# SparkFun_MP3_Breakout-VS1033D.net
KiCad netlist of a schematic drawn in EAGLE
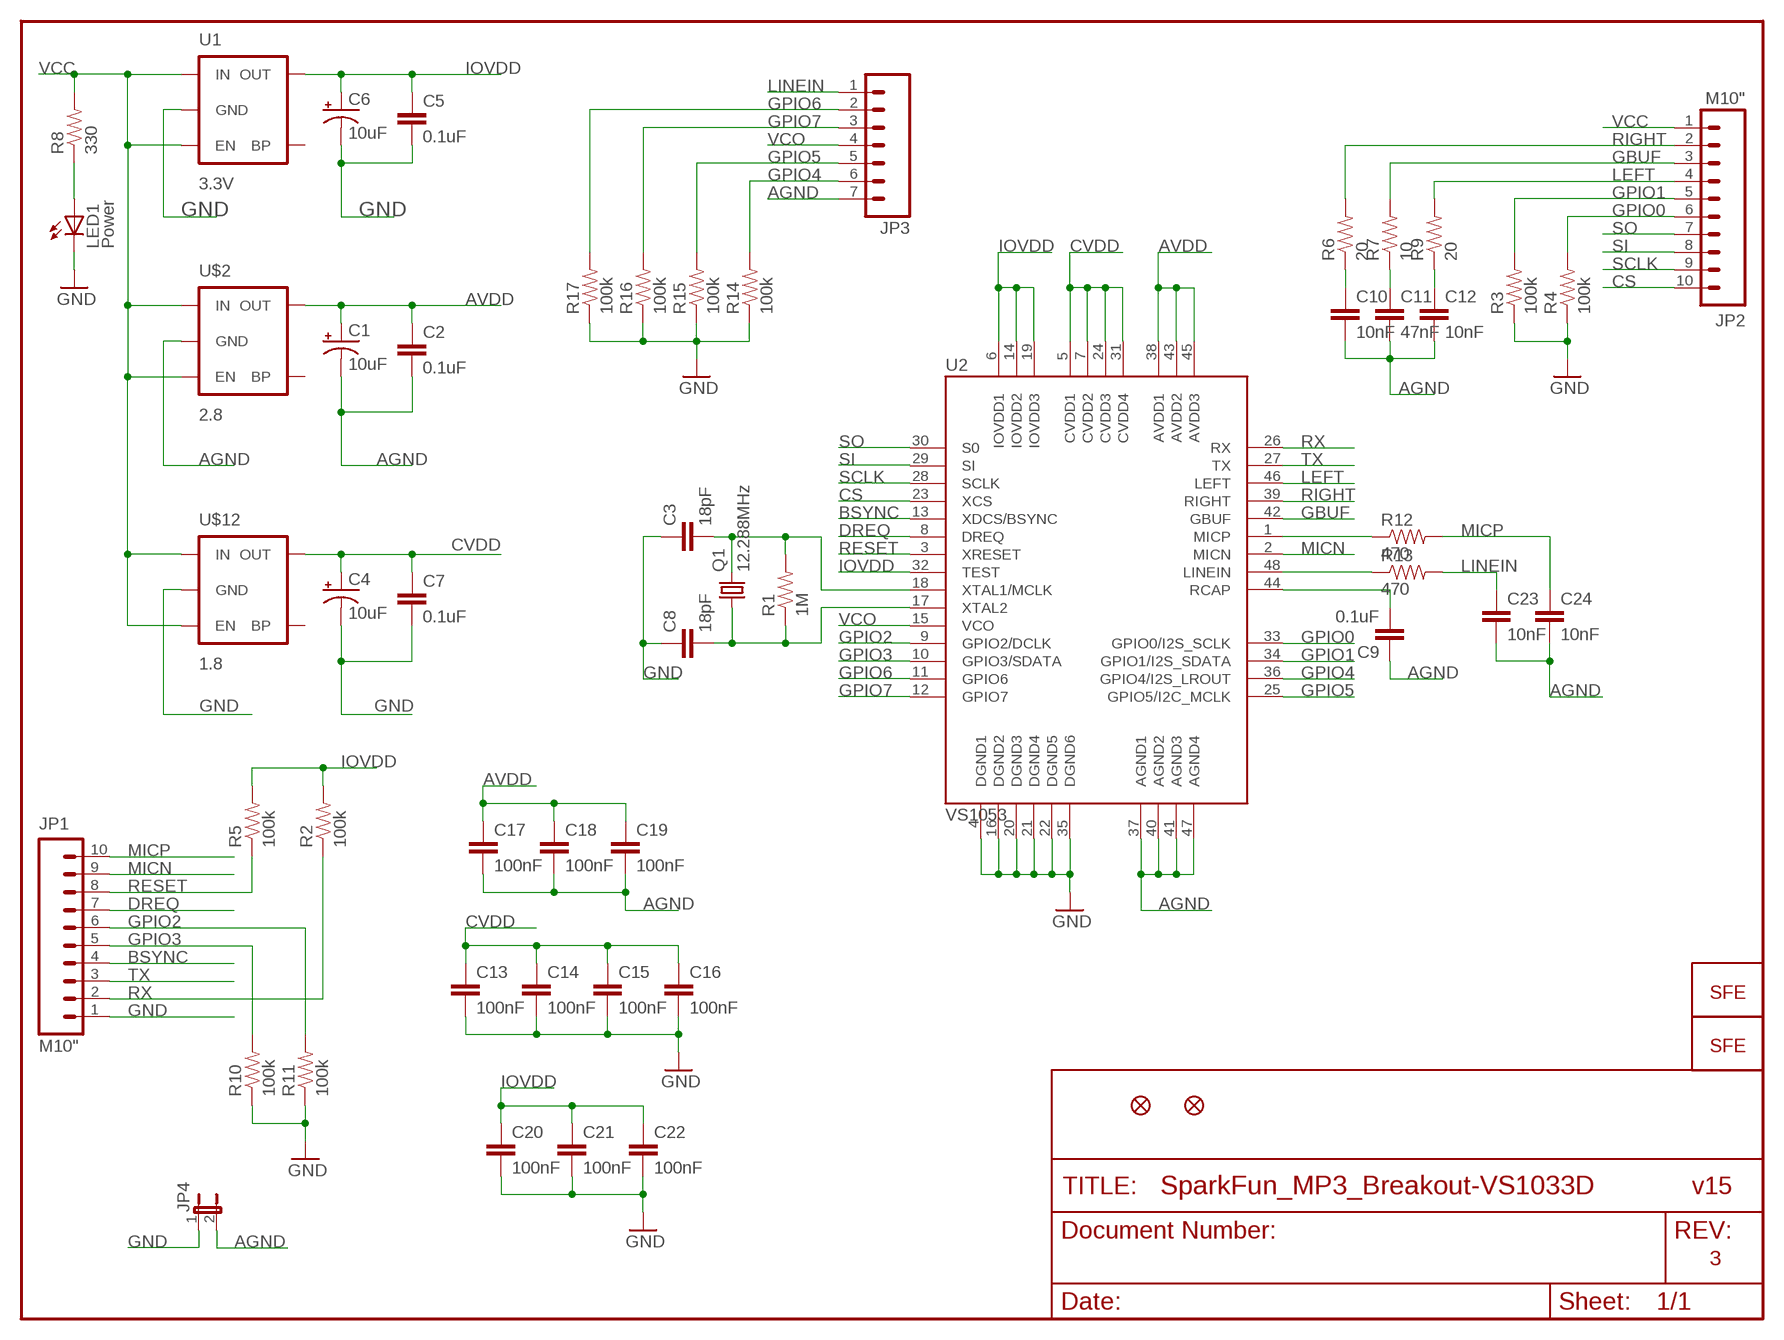
[diagram p0: schematic, sheet 1]

(export (version "E")
  (design (tool "Eeschema 10.0.6"))
  (components
    (comp (ref "C1")
      (value "10uF")
      (footprint "eagle-import:EIA3216")
      (libsource (lib "eagle-import") (part "CAP_POL1206"))
    )
    (comp (ref "C2")
      (value "0.1uF")
      (footprint "eagle-import:0402-CAP")
      (libsource (lib "eagle-import") (part "CAP0402-CAP"))
    )
    (comp (ref "C3")
      (value "18pF")
      (footprint "eagle-import:0402-CAP")
      (libsource (lib "eagle-import") (part "CAP0402-CAP"))
    )
    (comp (ref "C4")
      (value "10uF")
      (footprint "eagle-import:EIA3216")
      (libsource (lib "eagle-import") (part "CAP_POL1206"))
    )
    (comp (ref "C5")
      (value "0.1uF")
      (footprint "eagle-import:0402-CAP")
      (libsource (lib "eagle-import") (part "CAP0402-CAP"))
    )
    (comp (ref "C6")
      (value "10uF")
      (footprint "eagle-import:EIA3216")
      (libsource (lib "eagle-import") (part "CAP_POL1206"))
    )
    (comp (ref "C7")
      (value "0.1uF")
      (footprint "eagle-import:0402-CAP")
      (libsource (lib "eagle-import") (part "CAP0402-CAP"))
    )
    (comp (ref "C8")
      (value "18pF")
      (footprint "eagle-import:0402-CAP")
      (libsource (lib "eagle-import") (part "CAP0402-CAP"))
    )
    (comp (ref "C9")
      (value "0.1uF")
      (footprint "eagle-import:0402-CAP")
      (libsource (lib "eagle-import") (part "CAP0402-CAP"))
    )
    (comp (ref "C10")
      (value "10nF")
      (footprint "eagle-import:0402-CAP")
      (libsource (lib "eagle-import") (part "CAP0402-CAP"))
    )
    (comp (ref "C11")
      (value "47nF")
      (footprint "eagle-import:0402-CAP")
      (libsource (lib "eagle-import") (part "CAP0402-CAP"))
    )
    (comp (ref "C12")
      (value "10nF")
      (footprint "eagle-import:0402-CAP")
      (libsource (lib "eagle-import") (part "CAP0402-CAP"))
    )
    (comp (ref "C13")
      (value "100nF")
      (footprint "eagle-import:0402-CAP")
      (libsource (lib "eagle-import") (part "CAP0402-CAP"))
    )
    (comp (ref "C14")
      (value "100nF")
      (footprint "eagle-import:0402-CAP")
      (libsource (lib "eagle-import") (part "CAP0402-CAP"))
    )
    (comp (ref "C15")
      (value "100nF")
      (footprint "eagle-import:0402-CAP")
      (libsource (lib "eagle-import") (part "CAP0402-CAP"))
    )
    (comp (ref "C16")
      (value "100nF")
      (footprint "eagle-import:0402-CAP")
      (libsource (lib "eagle-import") (part "CAP0402-CAP"))
    )
    (comp (ref "C17")
      (value "100nF")
      (footprint "eagle-import:0402-CAP")
      (libsource (lib "eagle-import") (part "CAP0402-CAP"))
    )
    (comp (ref "C18")
      (value "100nF")
      (footprint "eagle-import:0402-CAP")
      (libsource (lib "eagle-import") (part "CAP0402-CAP"))
    )
    (comp (ref "C19")
      (value "100nF")
      (footprint "eagle-import:0402-CAP")
      (libsource (lib "eagle-import") (part "CAP0402-CAP"))
    )
    (comp (ref "C20")
      (value "100nF")
      (footprint "eagle-import:0402-CAP")
      (libsource (lib "eagle-import") (part "CAP0402-CAP"))
    )
    (comp (ref "C21")
      (value "100nF")
      (footprint "eagle-import:0402-CAP")
      (libsource (lib "eagle-import") (part "CAP0402-CAP"))
    )
    (comp (ref "C22")
      (value "100nF")
      (footprint "eagle-import:0402-CAP")
      (libsource (lib "eagle-import") (part "CAP0402-CAP"))
    )
    (comp (ref "C23")
      (value "10nF")
      (footprint "eagle-import:0402-CAP")
      (libsource (lib "eagle-import") (part "CAP0402-CAP"))
    )
    (comp (ref "C24")
      (value "10nF")
      (footprint "eagle-import:0402-CAP")
      (libsource (lib "eagle-import") (part "CAP0402-CAP"))
    )
    (comp (ref "JP1")
      (value "M10\"")
      (footprint "eagle-import:1X10")
      (libsource (lib "eagle-import") (part "M10{dblquote}"))
    )
    (comp (ref "JP2")
      (value "M10\"")
      (footprint "eagle-import:1X10")
      (libsource (lib "eagle-import") (part "M10{dblquote}"))
    )
    (comp (ref "JP3")
      (value "M07")
      (footprint "eagle-import:1X07")
      (libsource (lib "eagle-import") (part "M07"))
    )
    (comp (ref "JP4")
      (value "JUMPER-2SMD-NC")
      (footprint "eagle-import:SJ_2S")
      (libsource (lib "eagle-import") (part "JUMPER-2SMD-NC"))
    )
    (comp (ref "LED1")
      (value "Power")
      (footprint "eagle-import:LED-0603")
      (libsource (lib "eagle-import") (part "LED0603"))
    )
    (comp (ref "Q1")
      (value "12.288MHz")
      (footprint "eagle-import:CRYSTAL-SMD-5X3")
      (libsource (lib "eagle-import") (part "CRYSTAL5X3"))
    )
    (comp (ref "R1")
      (value "1M")
      (footprint "eagle-import:0402-RES")
      (libsource (lib "eagle-import") (part "RESISTOR0402-RES"))
    )
    (comp (ref "R2")
      (value "100k")
      (footprint "eagle-import:0402-RES")
      (libsource (lib "eagle-import") (part "RESISTOR0402-RES"))
    )
    (comp (ref "R3")
      (value "100k")
      (footprint "eagle-import:0402-RES")
      (libsource (lib "eagle-import") (part "RESISTOR0402-RES"))
    )
    (comp (ref "R4")
      (value "100k")
      (footprint "eagle-import:0402-RES")
      (libsource (lib "eagle-import") (part "RESISTOR0402-RES"))
    )
    (comp (ref "R5")
      (value "100k")
      (footprint "eagle-import:0402-RES")
      (libsource (lib "eagle-import") (part "RESISTOR0402-RES"))
    )
    (comp (ref "R6")
      (value "20")
      (footprint "eagle-import:0402-RES")
      (libsource (lib "eagle-import") (part "RESISTOR0402-RES"))
    )
    (comp (ref "R7")
      (value "10")
      (footprint "eagle-import:0402-RES")
      (libsource (lib "eagle-import") (part "RESISTOR0402-RES"))
    )
    (comp (ref "R8")
      (value "330")
      (footprint "eagle-import:0402-RES")
      (libsource (lib "eagle-import") (part "RESISTOR0402-RES"))
    )
    (comp (ref "R9")
      (value "20")
      (footprint "eagle-import:0402-RES")
      (libsource (lib "eagle-import") (part "RESISTOR0402-RES"))
    )
    (comp (ref "R10")
      (value "100k")
      (footprint "eagle-import:0402-RES")
      (libsource (lib "eagle-import") (part "RESISTOR0402-RES"))
    )
    (comp (ref "R11")
      (value "100k")
      (footprint "eagle-import:0402-RES")
      (libsource (lib "eagle-import") (part "RESISTOR0402-RES"))
    )
    (comp (ref "R12")
      (value "470")
      (footprint "eagle-import:0402-RES")
      (libsource (lib "eagle-import") (part "RESISTOR0402-RES"))
    )
    (comp (ref "R13")
      (value "470")
      (footprint "eagle-import:0402-RES")
      (libsource (lib "eagle-import") (part "RESISTOR0402-RES"))
    )
    (comp (ref "R14")
      (value "100k")
      (footprint "eagle-import:0402-RES")
      (libsource (lib "eagle-import") (part "RESISTOR0402-RES"))
    )
    (comp (ref "R15")
      (value "100k")
      (footprint "eagle-import:0402-RES")
      (libsource (lib "eagle-import") (part "RESISTOR0402-RES"))
    )
    (comp (ref "R16")
      (value "100k")
      (footprint "eagle-import:0402-RES")
      (libsource (lib "eagle-import") (part "RESISTOR0402-RES"))
    )
    (comp (ref "R17")
      (value "100k")
      (footprint "eagle-import:0402-RES")
      (libsource (lib "eagle-import") (part "RESISTOR0402-RES"))
    )
    (comp (ref "U$2")
      (value "2.8")
      (footprint "eagle-import:SC70")
      (libsource (lib "eagle-import") (part "V_REG_LDOSMD2"))
    )
    (comp (ref "U$4")
      (value "FIDUCIAL1X2")
      (footprint "eagle-import:FIDUCIAL-1X2")
      (libsource (lib "eagle-import") (part "FIDUCIAL1X2"))
    )
    (comp (ref "U$5")
      (value "FIDUCIAL1X2")
      (footprint "eagle-import:FIDUCIAL-1X2")
      (libsource (lib "eagle-import") (part "FIDUCIAL1X2"))
    )
    (comp (ref "U$6")
      (value "LOGO-SFESK")
      (footprint "eagle-import:SFE-LOGO-FLAME")
      (libsource (lib "eagle-import") (part "LOGO-SFESK"))
    )
    (comp (ref "U$7")
      (value "LOGO-SFENEW")
      (footprint "eagle-import:SFE-NEW-WEBLOGO")
      (libsource (lib "eagle-import") (part "LOGO-SFENEW"))
    )
    (comp (ref "U$12")
      (value "1.8")
      (footprint "eagle-import:SC70")
      (libsource (lib "eagle-import") (part "V_REG_LDOSMD2"))
    )
    (comp (ref "U1")
      (value "3.3V")
      (footprint "eagle-import:SOT23-5")
      (libsource (lib "eagle-import") (part "V_REG_LDOSMD"))
    )
    (comp (ref "U2")
      (value "VS1053")
      (footprint "eagle-import:LQFP-48")
      (libsource (lib "eagle-import") (part "VS1033"))
    )
  )
  (nets
    (net (code "1") (name "/AGND") (class "Default")
      (node (ref "C1") (pin "C") (pinfunction "-_C") (pintype "passive"))
      (node (ref "C10") (pin "2") (pinfunction "2_2") (pintype "passive"))
      (node (ref "C11") (pin "2") (pinfunction "2_2") (pintype "passive"))
      (node (ref "C12") (pin "2") (pinfunction "2_2") (pintype "passive"))
      (node (ref "C17") (pin "2") (pinfunction "2_2") (pintype "passive"))
      (node (ref "C18") (pin "2") (pinfunction "2_2") (pintype "passive"))
      (node (ref "C19") (pin "2") (pinfunction "2_2") (pintype "passive"))
      (node (ref "C2") (pin "2") (pinfunction "2_2") (pintype "passive"))
      (node (ref "C23") (pin "2") (pinfunction "2_2") (pintype "passive"))
      (node (ref "C24") (pin "2") (pinfunction "2_2") (pintype "passive"))
      (node (ref "C9") (pin "1") (pinfunction "1_1") (pintype "passive"))
      (node (ref "JP3") (pin "7") (pinfunction "7_7") (pintype "passive"))
      (node (ref "JP4") (pin "2") (pinfunction "2_2") (pintype "passive"))
      (node (ref "U$2") (pin "2") (pinfunction "GND_2") (pintype "input"))
      (node (ref "U2") (pin "37") (pinfunction "AGND1_37") (pintype "bidirectional"))
      (node (ref "U2") (pin "40") (pinfunction "AGND2_40") (pintype "bidirectional"))
      (node (ref "U2") (pin "41") (pinfunction "AGND3_41") (pintype "bidirectional"))
      (node (ref "U2") (pin "47") (pinfunction "AGND4_47") (pintype "bidirectional"))
    )
    (net (code "2") (name "/AVDD") (class "Default")
      (node (ref "C1") (pin "A") (pinfunction "+_A") (pintype "passive"))
      (node (ref "C17") (pin "1") (pinfunction "1_1") (pintype "passive"))
      (node (ref "C18") (pin "1") (pinfunction "1_1") (pintype "passive"))
      (node (ref "C19") (pin "1") (pinfunction "1_1") (pintype "passive"))
      (node (ref "C2") (pin "1") (pinfunction "1_1") (pintype "passive"))
      (node (ref "U$2") (pin "5") (pinfunction "OUT_5") (pintype "passive"))
      (node (ref "U2") (pin "38") (pinfunction "AVDD1_38") (pintype "bidirectional"))
      (node (ref "U2") (pin "43") (pinfunction "AVDD2_43") (pintype "bidirectional"))
      (node (ref "U2") (pin "45") (pinfunction "AVDD3_45") (pintype "bidirectional"))
    )
    (net (code "3") (name "/BSYNC") (class "Default")
      (node (ref "JP1") (pin "4") (pinfunction "4_4") (pintype "passive"))
      (node (ref "U2") (pin "13") (pinfunction "XDCS/BSYNC_13") (pintype "bidirectional"))
    )
    (net (code "4") (name "/CS") (class "Default")
      (node (ref "JP2") (pin "10") (pinfunction "10_10") (pintype "passive"))
      (node (ref "U2") (pin "23") (pinfunction "XCS_23") (pintype "bidirectional"))
    )
    (net (code "5") (name "/CVDD") (class "Default")
      (node (ref "C13") (pin "1") (pinfunction "1_1") (pintype "passive"))
      (node (ref "C14") (pin "1") (pinfunction "1_1") (pintype "passive"))
      (node (ref "C15") (pin "1") (pinfunction "1_1") (pintype "passive"))
      (node (ref "C16") (pin "1") (pinfunction "1_1") (pintype "passive"))
      (node (ref "C4") (pin "A") (pinfunction "+_A") (pintype "passive"))
      (node (ref "C7") (pin "1") (pinfunction "1_1") (pintype "passive"))
      (node (ref "U$12") (pin "5") (pinfunction "OUT_5") (pintype "passive"))
      (node (ref "U2") (pin "24") (pinfunction "CVDD3_24") (pintype "bidirectional"))
      (node (ref "U2") (pin "31") (pinfunction "CVDD4_31") (pintype "bidirectional"))
      (node (ref "U2") (pin "5") (pinfunction "CVDD1_5") (pintype "bidirectional"))
      (node (ref "U2") (pin "7") (pinfunction "CVDD2_7") (pintype "bidirectional"))
    )
    (net (code "6") (name "/DREQ") (class "Default")
      (node (ref "JP1") (pin "7") (pinfunction "7_7") (pintype "passive"))
      (node (ref "U2") (pin "8") (pinfunction "DREQ_8") (pintype "bidirectional"))
    )
    (net (code "7") (name "/GBUF") (class "Default")
      (node (ref "JP2") (pin "3") (pinfunction "3_3") (pintype "passive"))
      (node (ref "R7") (pin "2") (pinfunction "2_2") (pintype "passive"))
      (node (ref "U2") (pin "42") (pinfunction "GBUF_42") (pintype "bidirectional"))
    )
    (net (code "8") (name "/GPIO0") (class "Default")
      (node (ref "JP2") (pin "6") (pinfunction "6_6") (pintype "passive"))
      (node (ref "R4") (pin "2") (pinfunction "2_2") (pintype "passive"))
      (node (ref "U2") (pin "33") (pinfunction "GPIO0/I2S_SCLK_33") (pintype "bidirectional"))
    )
    (net (code "9") (name "/GPIO1") (class "Default")
      (node (ref "JP2") (pin "5") (pinfunction "5_5") (pintype "passive"))
      (node (ref "R3") (pin "2") (pinfunction "2_2") (pintype "passive"))
      (node (ref "U2") (pin "34") (pinfunction "GPIO1/I2S_SDATA_34") (pintype "bidirectional"))
    )
    (net (code "10") (name "/GPIO2") (class "Default")
      (node (ref "JP1") (pin "6") (pinfunction "6_6") (pintype "passive"))
      (node (ref "R11") (pin "2") (pinfunction "2_2") (pintype "passive"))
      (node (ref "U2") (pin "9") (pinfunction "GPIO2/DCLK_9") (pintype "bidirectional"))
    )
    (net (code "11") (name "/GPIO3") (class "Default")
      (node (ref "JP1") (pin "5") (pinfunction "5_5") (pintype "passive"))
      (node (ref "R10") (pin "2") (pinfunction "2_2") (pintype "passive"))
      (node (ref "U2") (pin "10") (pinfunction "GPIO3/SDATA_10") (pintype "bidirectional"))
    )
    (net (code "12") (name "/GPIO4") (class "Default")
      (node (ref "JP3") (pin "6") (pinfunction "6_6") (pintype "passive"))
      (node (ref "R14") (pin "2") (pinfunction "2_2") (pintype "passive"))
      (node (ref "U2") (pin "36") (pinfunction "GPIO4/I2S_LROUT_36") (pintype "bidirectional"))
    )
    (net (code "13") (name "/GPIO5") (class "Default")
      (node (ref "JP3") (pin "5") (pinfunction "5_5") (pintype "passive"))
      (node (ref "R15") (pin "2") (pinfunction "2_2") (pintype "passive"))
      (node (ref "U2") (pin "25") (pinfunction "GPIO5/I2C_MCLK_25") (pintype "bidirectional"))
    )
    (net (code "14") (name "/GPIO6") (class "Default")
      (node (ref "JP3") (pin "2") (pinfunction "2_2") (pintype "passive"))
      (node (ref "R17") (pin "2") (pinfunction "2_2") (pintype "passive"))
      (node (ref "U2") (pin "11") (pinfunction "GPIO6_11") (pintype "bidirectional"))
    )
    (net (code "15") (name "/GPIO7") (class "Default")
      (node (ref "JP3") (pin "3") (pinfunction "3_3") (pintype "passive"))
      (node (ref "R16") (pin "2") (pinfunction "2_2") (pintype "passive"))
      (node (ref "U2") (pin "12") (pinfunction "GPIO7_12") (pintype "bidirectional"))
    )
    (net (code "16") (name "/IOVDD") (class "Default")
      (node (ref "C20") (pin "1") (pinfunction "1_1") (pintype "passive"))
      (node (ref "C21") (pin "1") (pinfunction "1_1") (pintype "passive"))
      (node (ref "C22") (pin "1") (pinfunction "1_1") (pintype "passive"))
      (node (ref "C5") (pin "1") (pinfunction "1_1") (pintype "passive"))
      (node (ref "C6") (pin "A") (pinfunction "+_A") (pintype "passive"))
      (node (ref "R2") (pin "2") (pinfunction "2_2") (pintype "passive"))
      (node (ref "R5") (pin "2") (pinfunction "2_2") (pintype "passive"))
      (node (ref "U1") (pin "5") (pinfunction "OUT_5") (pintype "passive"))
      (node (ref "U2") (pin "14") (pinfunction "IOVDD2_14") (pintype "bidirectional"))
      (node (ref "U2") (pin "19") (pinfunction "IOVDD3_19") (pintype "bidirectional"))
      (node (ref "U2") (pin "32") (pinfunction "TEST_32") (pintype "bidirectional"))
      (node (ref "U2") (pin "6") (pinfunction "IOVDD1_6") (pintype "bidirectional"))
    )
    (net (code "17") (name "/LEFT") (class "Default")
      (node (ref "JP2") (pin "4") (pinfunction "4_4") (pintype "passive"))
      (node (ref "R9") (pin "2") (pinfunction "2_2") (pintype "passive"))
      (node (ref "U2") (pin "46") (pinfunction "LEFT_46") (pintype "bidirectional"))
    )
    (net (code "18") (name "/LINEIN") (class "Default")
      (node (ref "C23") (pin "1") (pinfunction "1_1") (pintype "passive"))
      (node (ref "JP3") (pin "1") (pinfunction "1_1") (pintype "passive"))
      (node (ref "R13") (pin "2") (pinfunction "2_2") (pintype "passive"))
    )
    (net (code "19") (name "/MICN") (class "Default")
      (node (ref "JP1") (pin "9") (pinfunction "9_9") (pintype "passive"))
      (node (ref "U2") (pin "2") (pinfunction "MICN_2") (pintype "bidirectional"))
    )
    (net (code "20") (name "/MICP") (class "Default")
      (node (ref "C24") (pin "1") (pinfunction "1_1") (pintype "passive"))
      (node (ref "JP1") (pin "10") (pinfunction "10_10") (pintype "passive"))
      (node (ref "R12") (pin "2") (pinfunction "2_2") (pintype "passive"))
    )
    (net (code "21") (name "/RESET") (class "Default")
      (node (ref "JP1") (pin "8") (pinfunction "8_8") (pintype "passive"))
      (node (ref "R5") (pin "1") (pinfunction "1_1") (pintype "passive"))
      (node (ref "U2") (pin "3") (pinfunction "XRESET_3") (pintype "bidirectional"))
    )
    (net (code "22") (name "/RIGHT") (class "Default")
      (node (ref "JP2") (pin "2") (pinfunction "2_2") (pintype "passive"))
      (node (ref "R6") (pin "2") (pinfunction "2_2") (pintype "passive"))
      (node (ref "U2") (pin "39") (pinfunction "RIGHT_39") (pintype "bidirectional"))
    )
    (net (code "23") (name "/RX") (class "Default")
      (node (ref "JP1") (pin "2") (pinfunction "2_2") (pintype "passive"))
      (node (ref "R2") (pin "1") (pinfunction "1_1") (pintype "passive"))
      (node (ref "U2") (pin "26") (pinfunction "RX_26") (pintype "bidirectional"))
    )
    (net (code "24") (name "/SCLK") (class "Default")
      (node (ref "JP2") (pin "9") (pinfunction "9_9") (pintype "passive"))
      (node (ref "U2") (pin "28") (pinfunction "SCLK_28") (pintype "bidirectional"))
    )
    (net (code "25") (name "/SI") (class "Default")
      (node (ref "JP2") (pin "8") (pinfunction "8_8") (pintype "passive"))
      (node (ref "U2") (pin "29") (pinfunction "SI_29") (pintype "bidirectional"))
    )
    (net (code "26") (name "/SO") (class "Default")
      (node (ref "JP2") (pin "7") (pinfunction "7_7") (pintype "passive"))
      (node (ref "U2") (pin "30") (pinfunction "S0_30") (pintype "bidirectional"))
    )
    (net (code "27") (name "/TX") (class "Default")
      (node (ref "JP1") (pin "3") (pinfunction "3_3") (pintype "passive"))
      (node (ref "U2") (pin "27") (pinfunction "TX_27") (pintype "bidirectional"))
    )
    (net (code "28") (name "/VCC") (class "Default")
      (node (ref "JP2") (pin "1") (pinfunction "1_1") (pintype "passive"))
      (node (ref "R8") (pin "2") (pinfunction "2_2") (pintype "passive"))
      (node (ref "U$12") (pin "1") (pinfunction "IN_1") (pintype "input"))
      (node (ref "U$12") (pin "3") (pinfunction "EN_3") (pintype "input"))
      (node (ref "U$2") (pin "1") (pinfunction "IN_1") (pintype "input"))
      (node (ref "U$2") (pin "3") (pinfunction "EN_3") (pintype "input"))
      (node (ref "U1") (pin "1") (pinfunction "IN_1") (pintype "input"))
      (node (ref "U1") (pin "3") (pinfunction "EN_3") (pintype "input"))
    )
    (net (code "29") (name "/VCO") (class "Default")
      (node (ref "JP3") (pin "4") (pinfunction "4_4") (pintype "passive"))
      (node (ref "U2") (pin "15") (pinfunction "VCO_15") (pintype "bidirectional"))
    )
    (net (code "30") (name "GND") (class "Default")
      (node (ref "C13") (pin "2") (pinfunction "2_2") (pintype "passive"))
      (node (ref "C14") (pin "2") (pinfunction "2_2") (pintype "passive"))
      (node (ref "C15") (pin "2") (pinfunction "2_2") (pintype "passive"))
      (node (ref "C16") (pin "2") (pinfunction "2_2") (pintype "passive"))
      (node (ref "C20") (pin "2") (pinfunction "2_2") (pintype "passive"))
      (node (ref "C21") (pin "2") (pinfunction "2_2") (pintype "passive"))
      (node (ref "C22") (pin "2") (pinfunction "2_2") (pintype "passive"))
      (node (ref "C3") (pin "1") (pinfunction "1_1") (pintype "passive"))
      (node (ref "C4") (pin "C") (pinfunction "-_C") (pintype "passive"))
      (node (ref "C5") (pin "2") (pinfunction "2_2") (pintype "passive"))
      (node (ref "C6") (pin "C") (pinfunction "-_C") (pintype "passive"))
      (node (ref "C7") (pin "2") (pinfunction "2_2") (pintype "passive"))
      (node (ref "C8") (pin "1") (pinfunction "1_1") (pintype "passive"))
      (node (ref "JP1") (pin "1") (pinfunction "1_1") (pintype "passive"))
      (node (ref "JP4") (pin "1") (pinfunction "1_1") (pintype "passive"))
      (node (ref "LED1") (pin "C") (pinfunction "C_C") (pintype "passive"))
      (node (ref "R10") (pin "1") (pinfunction "1_1") (pintype "passive"))
      (node (ref "R11") (pin "1") (pinfunction "1_1") (pintype "passive"))
      (node (ref "R14") (pin "1") (pinfunction "1_1") (pintype "passive"))
      (node (ref "R15") (pin "1") (pinfunction "1_1") (pintype "passive"))
      (node (ref "R16") (pin "1") (pinfunction "1_1") (pintype "passive"))
      (node (ref "R17") (pin "1") (pinfunction "1_1") (pintype "passive"))
      (node (ref "R3") (pin "1") (pinfunction "1_1") (pintype "passive"))
      (node (ref "R4") (pin "1") (pinfunction "1_1") (pintype "passive"))
      (node (ref "U$12") (pin "2") (pinfunction "GND_2") (pintype "input"))
      (node (ref "U1") (pin "2") (pinfunction "GND_2") (pintype "input"))
      (node (ref "U2") (pin "16") (pinfunction "DGND2_16") (pintype "bidirectional"))
      (node (ref "U2") (pin "20") (pinfunction "DGND3_20") (pintype "bidirectional"))
      (node (ref "U2") (pin "21") (pinfunction "DGND4_21") (pintype "bidirectional"))
      (node (ref "U2") (pin "22") (pinfunction "DGND5_22") (pintype "bidirectional"))
      (node (ref "U2") (pin "35") (pinfunction "DGND6_35") (pintype "bidirectional"))
      (node (ref "U2") (pin "4") (pinfunction "DGND1_4") (pintype "bidirectional"))
    )
    (net (code "31") (name "Net-(C10-Pad1)") (class "Default")
      (node (ref "C10") (pin "1") (pinfunction "1_1") (pintype "passive"))
      (node (ref "R6") (pin "1") (pinfunction "1_1") (pintype "passive"))
    )
    (net (code "32") (name "Net-(C11-Pad1)") (class "Default")
      (node (ref "C11") (pin "1") (pinfunction "1_1") (pintype "passive"))
      (node (ref "R7") (pin "1") (pinfunction "1_1") (pintype "passive"))
    )
    (net (code "33") (name "Net-(C12-Pad1)") (class "Default")
      (node (ref "C12") (pin "1") (pinfunction "1_1") (pintype "passive"))
      (node (ref "R9") (pin "1") (pinfunction "1_1") (pintype "passive"))
    )
    (net (code "34") (name "Net-(LED1-PadA)") (class "Default")
      (node (ref "LED1") (pin "A") (pinfunction "A_A") (pintype "passive"))
      (node (ref "R8") (pin "1") (pinfunction "1_1") (pintype "passive"))
    )
    (net (code "35") (name "Net-(Q1-2)") (class "Default")
      (node (ref "C3") (pin "2") (pinfunction "2_2") (pintype "passive"))
      (node (ref "Q1") (pin "3") (pinfunction "2_3") (pintype "passive"))
      (node (ref "R1") (pin "2") (pinfunction "2_2") (pintype "passive"))
      (node (ref "U2") (pin "18") (pinfunction "XTAL1/MCLK_18") (pintype "bidirectional"))
    )
    (net (code "36") (name "Net-(U2-LINEIN)") (class "Default")
      (node (ref "R13") (pin "1") (pinfunction "1_1") (pintype "passive"))
      (node (ref "U2") (pin "48") (pinfunction "LINEIN_48") (pintype "bidirectional"))
    )
    (net (code "37") (name "Net-(U2-MICP)") (class "Default")
      (node (ref "R12") (pin "1") (pinfunction "1_1") (pintype "passive"))
      (node (ref "U2") (pin "1") (pinfunction "MICP_1") (pintype "bidirectional"))
    )
    (net (code "38") (name "Net-(U2-RCAP)") (class "Default")
      (node (ref "C9") (pin "2") (pinfunction "2_2") (pintype "passive"))
      (node (ref "U2") (pin "44") (pinfunction "RCAP_44") (pintype "bidirectional"))
    )
    (net (code "39") (name "Net-(U2-XTAL2)") (class "Default")
      (node (ref "C8") (pin "2") (pinfunction "2_2") (pintype "passive"))
      (node (ref "Q1") (pin "1") (pinfunction "1_1") (pintype "passive"))
      (node (ref "R1") (pin "1") (pinfunction "1_1") (pintype "passive"))
      (node (ref "U2") (pin "17") (pinfunction "XTAL2_17") (pintype "bidirectional"))
    )
    (net (code "40") (name "unconnected-(U$2-BP-Pad4)") (class "Default")
      (node (ref "U$2") (pin "4") (pinfunction "BP_4") (pintype "input"))
    )
    (net (code "41") (name "unconnected-(U$12-BP-Pad4)") (class "Default")
      (node (ref "U$12") (pin "4") (pinfunction "BP_4") (pintype "input"))
    )
    (net (code "42") (name "unconnected-(U1-BP-Pad4)") (class "Default")
      (node (ref "U1") (pin "4") (pinfunction "BP_4") (pintype "input"))
    )
  )
)
